# CH32V307VCT6-R2.net
KiCad netlist of a schematic drawn in Altium Designer
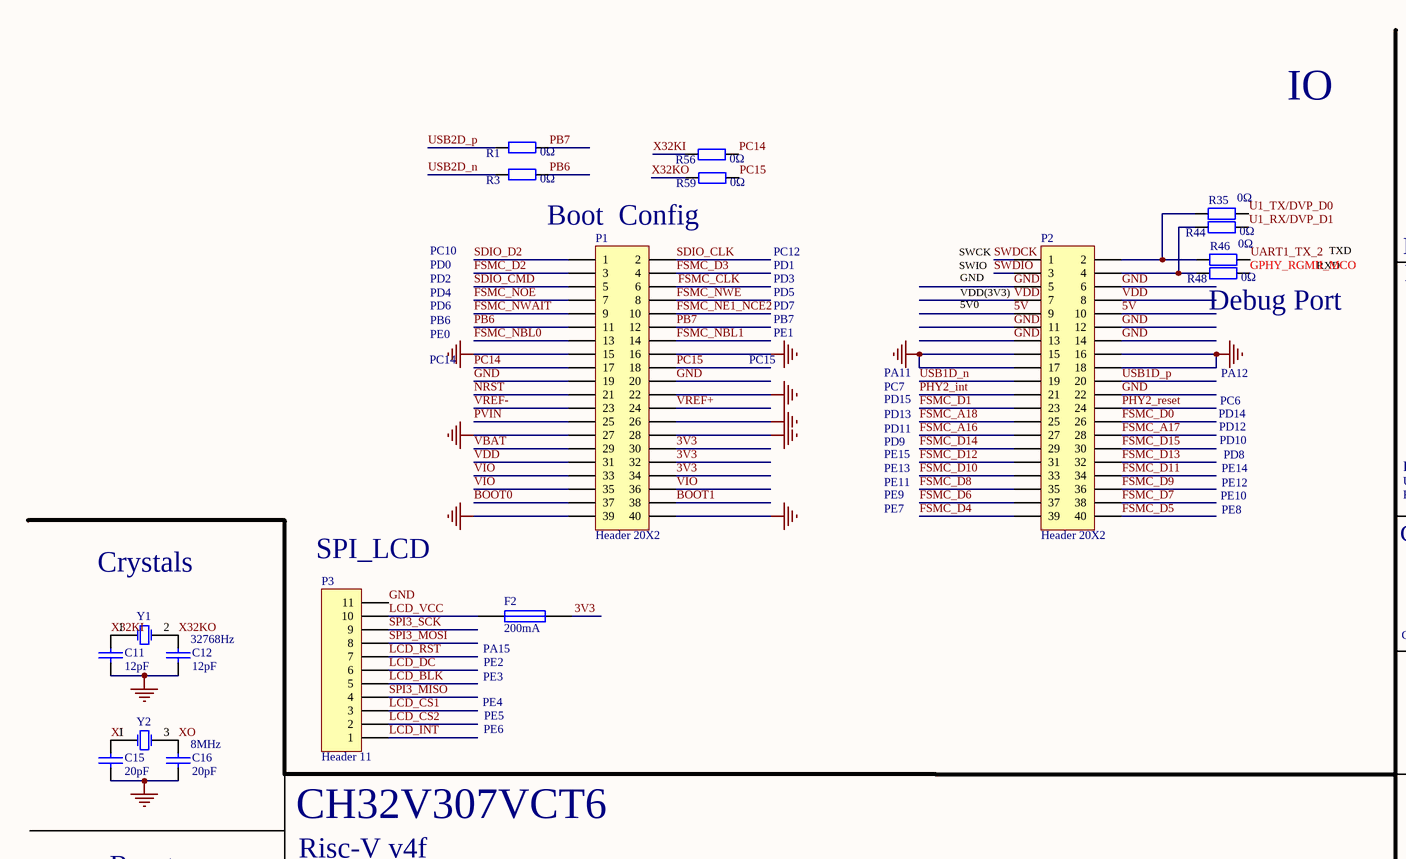
[diagram p0: CH32V307VCT6-R2.SchDoc, top left]
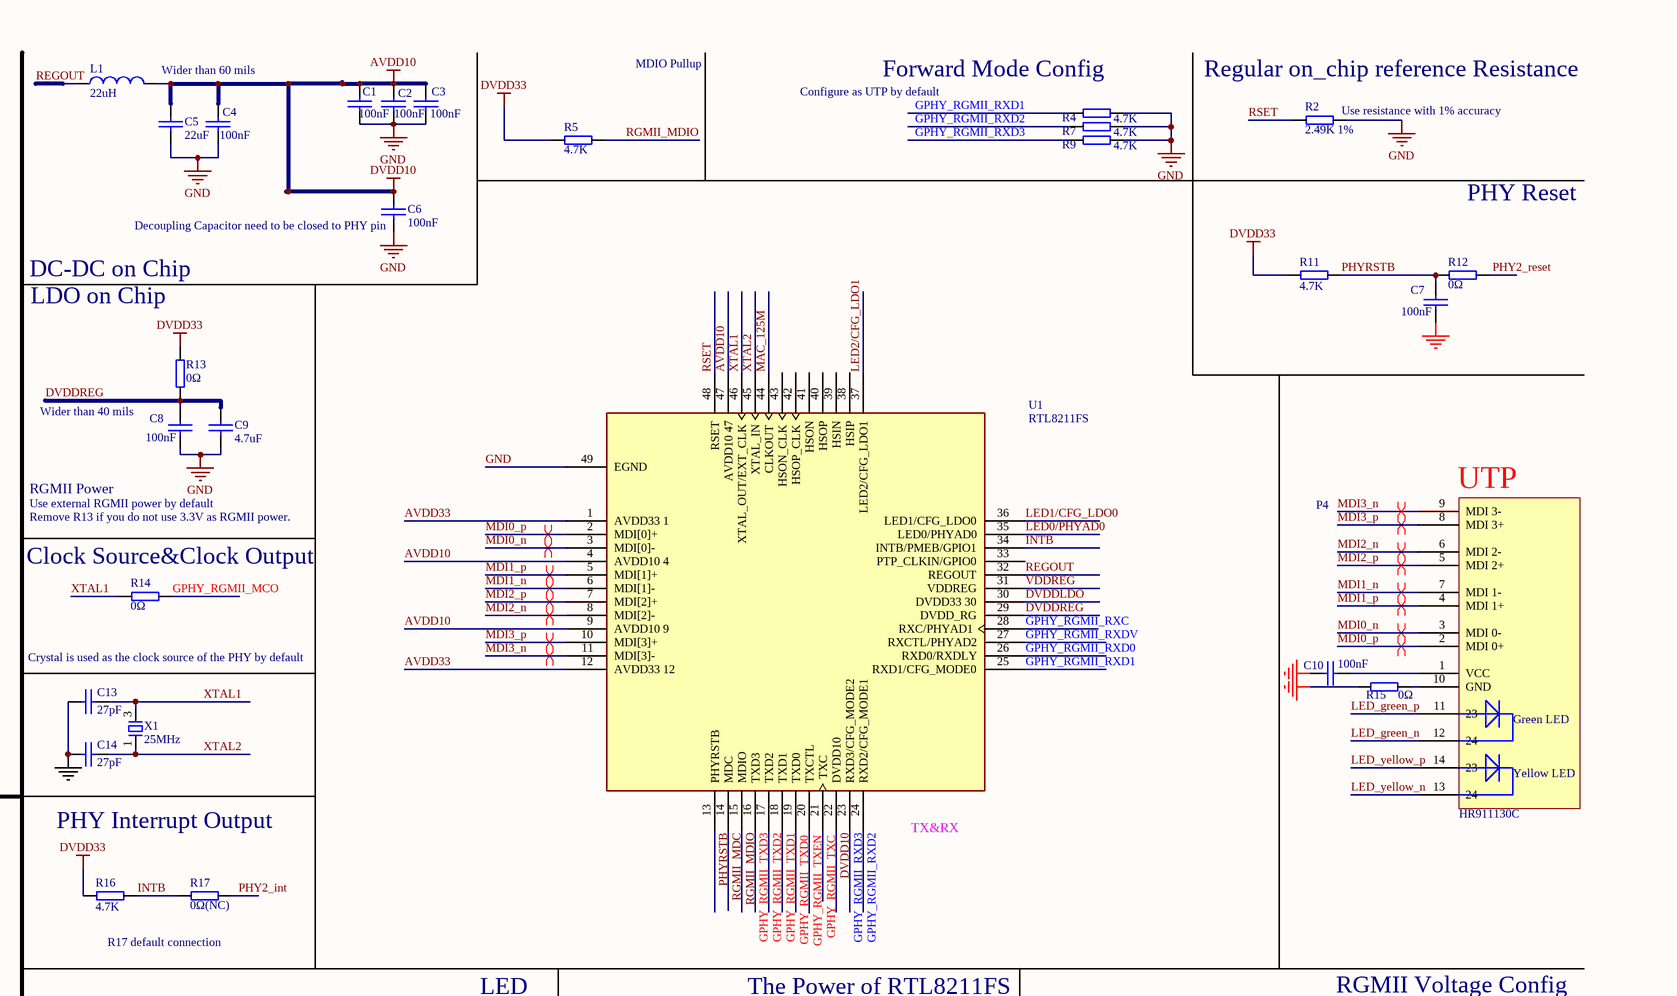
[diagram p1: CH32V307VCT6-R2.SchDoc, top right]
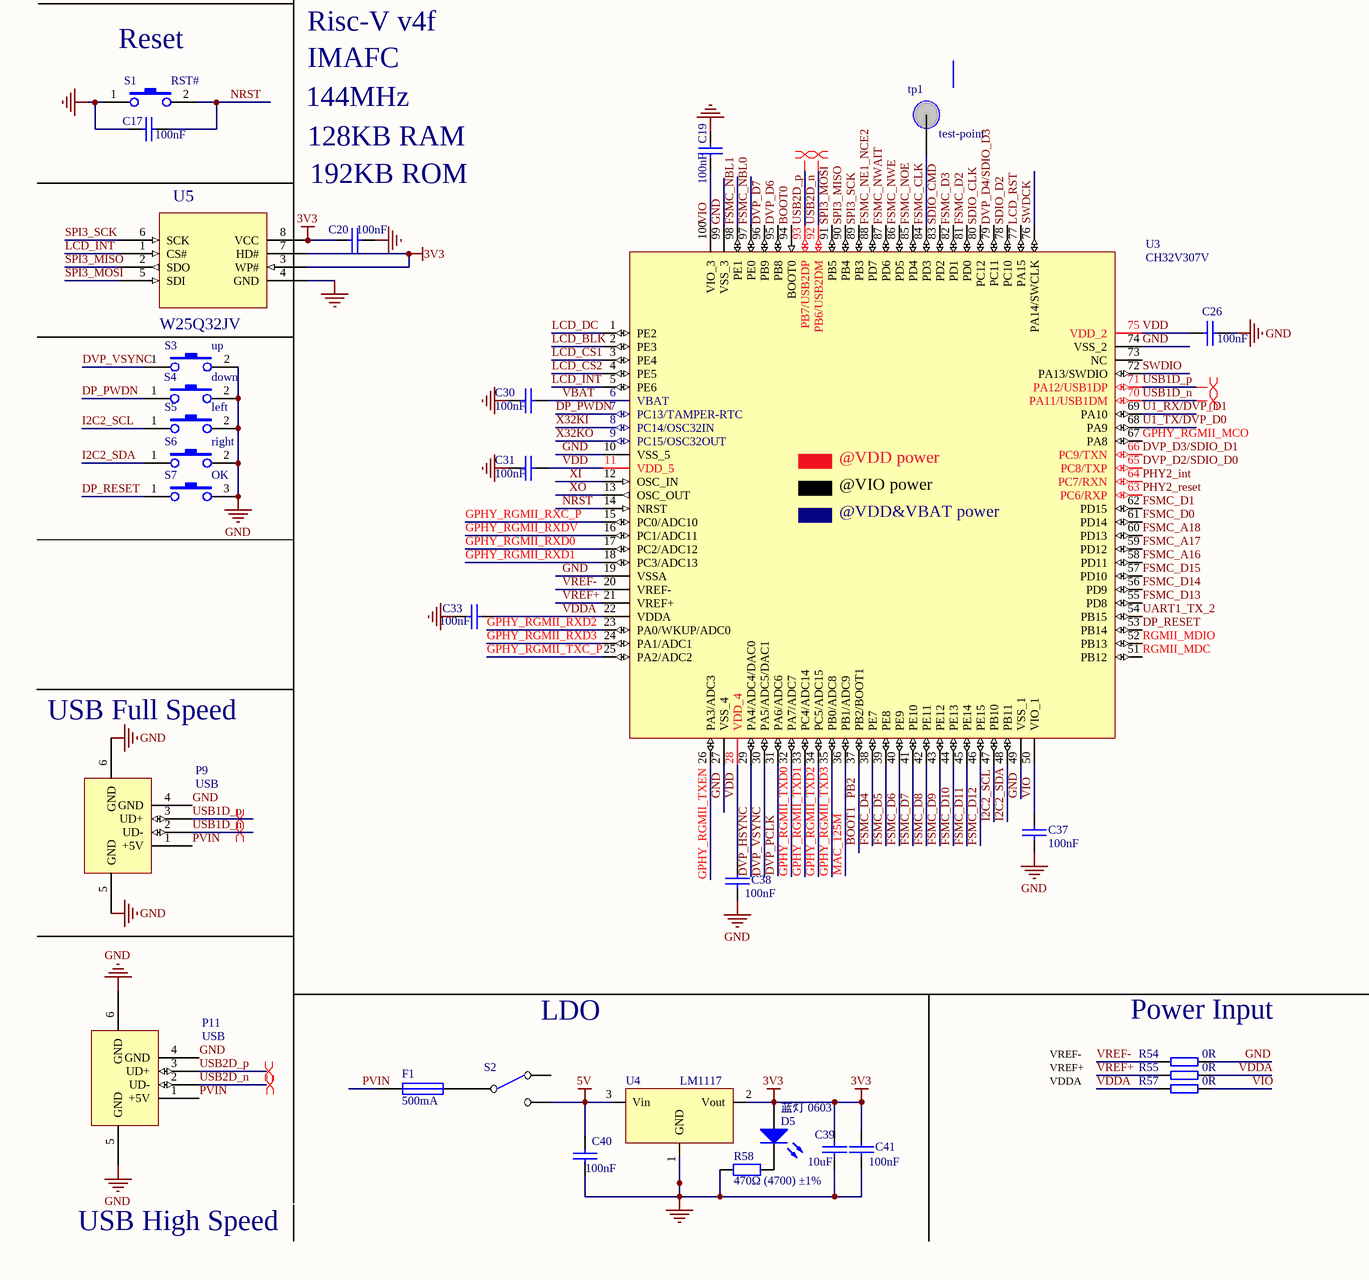
[diagram p2: CH32V307VCT6-R2.SchDoc, bottom left]
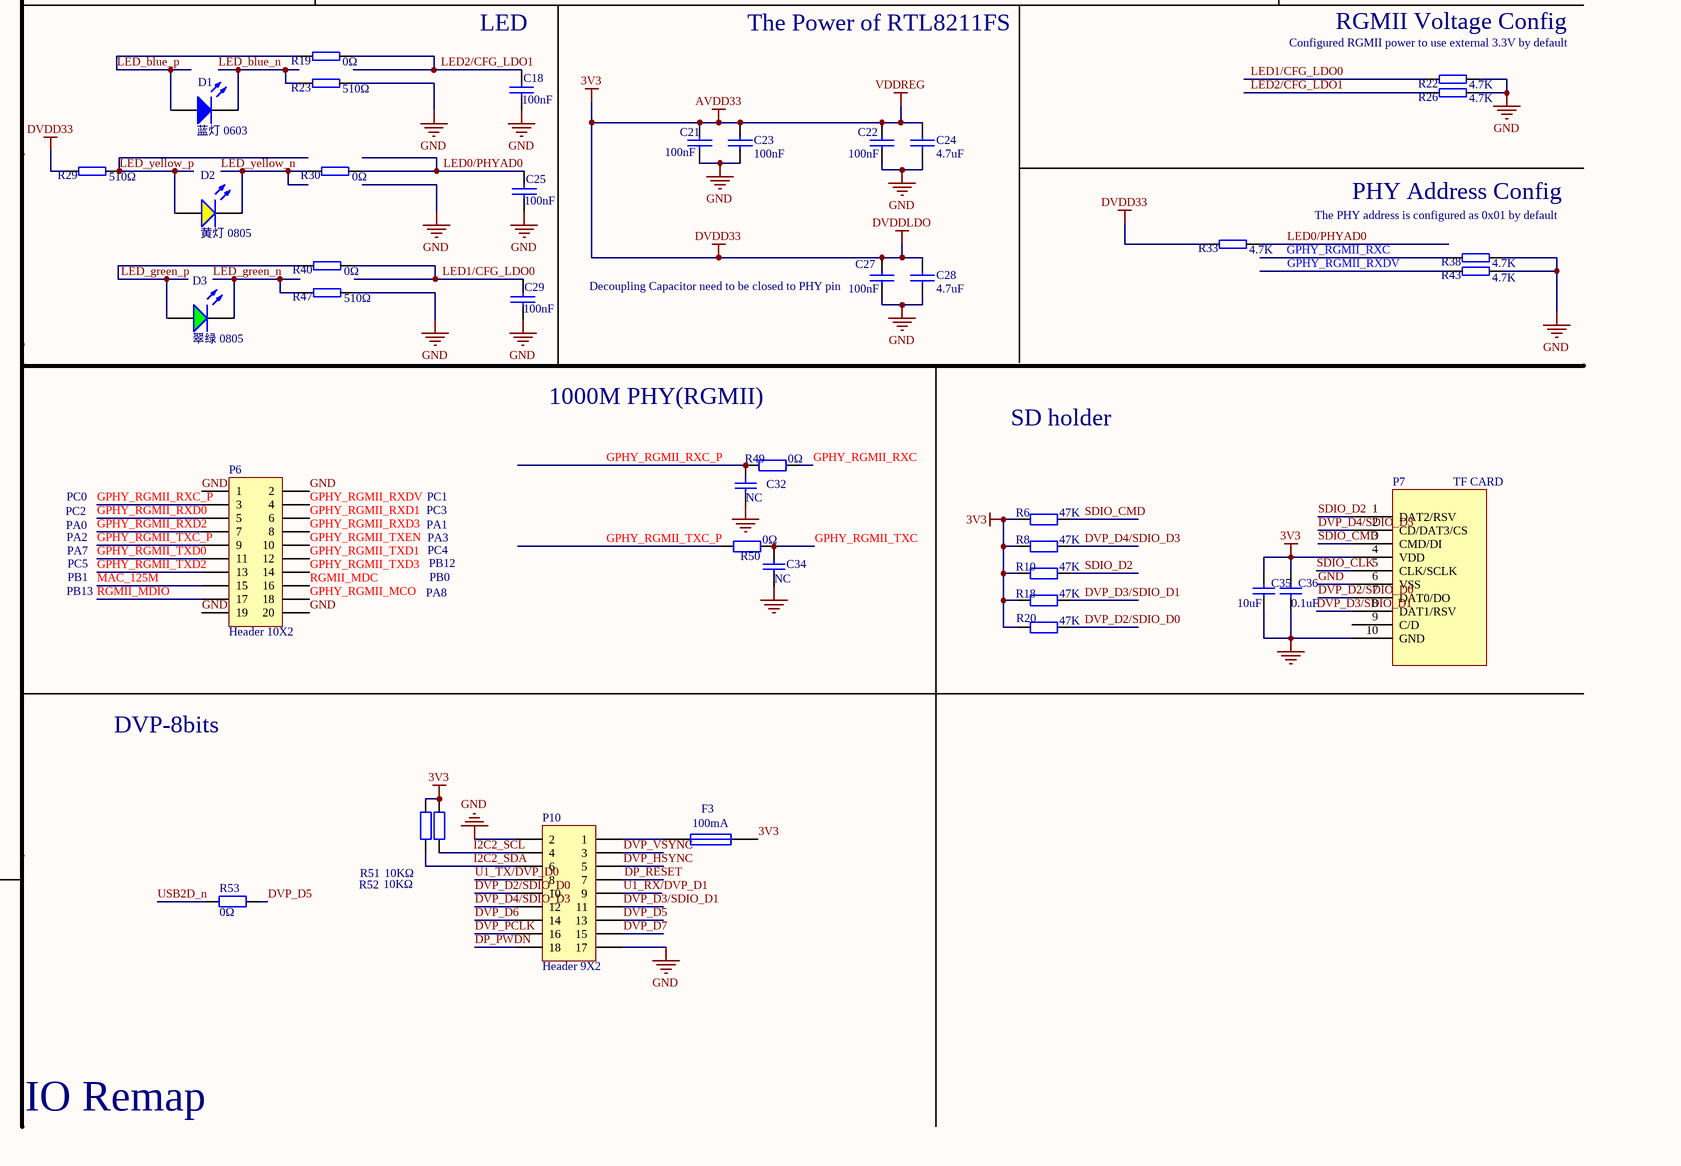
[diagram p3: CH32V307VCT6-R2.SchDoc, bottom right]

(export (version "E")
  (design (tool "Eeschema 10.0.6"))
  (components
    (comp (ref "C1")
      (value "100nF")
      (footprint "0603_C")
      (description "Capacitor")
      (libsource (lib "*") (part "CAP"))
    )
    (comp (ref "C2")
      (value "100nF")
      (footprint "0603_C")
      (description "Capacitor")
      (libsource (lib "*") (part "CAP"))
    )
    (comp (ref "C3")
      (value "100nF")
      (footprint "0603_C")
      (description "Capacitor")
      (libsource (lib "*") (part "CAP"))
    )
    (comp (ref "C4")
      (value "100nF")
      (footprint "0603_C")
      (description "Capacitor")
      (libsource (lib "*") (part "CAP"))
    )
    (comp (ref "C5")
      (value "22uF")
      (footprint "0805_C")
      (description "Capacitor")
      (libsource (lib "wch_sch_others") (part "CAP"))
    )
    (comp (ref "C6")
      (value "100nF")
      (footprint "0603_C")
      (description "Capacitor")
      (libsource (lib "*") (part "CAP"))
    )
    (comp (ref "C7")
      (value "100nF")
      (footprint "0603_C")
      (description "Capacitor")
      (libsource (lib "*") (part "CAP"))
    )
    (comp (ref "C8")
      (value "100nF")
      (footprint "0603_C")
      (description "Capacitor")
      (libsource (lib "*") (part "CAP"))
    )
    (comp (ref "C9")
      (value "4.7uF")
      (footprint "0603_C")
      (description "Capacitor")
      (libsource (lib "wch_sch_others") (part "CAP"))
    )
    (comp (ref "C10")
      (value "100nF")
      (footprint "0603_C")
      (description "Capacitor")
      (libsource (lib "*") (part "CAP"))
    )
    (comp (ref "C11")
      (value "12pF")
      (footprint "0603_C")
      (description "Capacitor")
      (libsource (lib "*") (part "CAP"))
    )
    (comp (ref "C12")
      (value "12pF")
      (footprint "0603_C")
      (description "Capacitor")
      (libsource (lib "*") (part "CAP"))
    )
    (comp (ref "C13")
      (value "27pF")
      (footprint "0603_C")
      (description "Capacitor")
      (libsource (lib "wch_sch_others") (part "CAP"))
    )
    (comp (ref "C14")
      (value "27pF")
      (footprint "0603_C")
      (description "Capacitor")
      (libsource (lib "wch_sch_others") (part "CAP"))
    )
    (comp (ref "C15")
      (value "20pF")
      (footprint "0603_C")
      (description "Capacitor")
      (libsource (lib "*") (part "CAP"))
    )
    (comp (ref "C16")
      (value "20pF")
      (footprint "0603_C")
      (description "Capacitor")
      (libsource (lib "*") (part "CAP"))
    )
    (comp (ref "C17")
      (value "100nF")
      (footprint "0603_C")
      (description "Capacitor")
      (libsource (lib "") (part "CAP_1"))
    )
    (comp (ref "C18")
      (value "100nF")
      (footprint "0603_C")
      (description "Capacitor")
      (libsource (lib "*") (part "CAP"))
    )
    (comp (ref "C19")
      (value "100nF")
      (footprint "0603_C")
      (description "Capacitor")
      (libsource (lib "*") (part "CAP"))
    )
    (comp (ref "C20")
      (value "100nF")
      (footprint "0603_C")
      (description "Capacitor")
      (libsource (lib "*") (part "CAP"))
    )
    (comp (ref "C21")
      (value "100nF")
      (footprint "0603_C")
      (description "Capacitor")
      (libsource (lib "*") (part "CAP"))
    )
    (comp (ref "C22")
      (value "100nF")
      (footprint "0603_C")
      (description "Capacitor")
      (libsource (lib "*") (part "CAP"))
    )
    (comp (ref "C23")
      (value "100nF")
      (footprint "0603_C")
      (description "Capacitor")
      (libsource (lib "*") (part "CAP"))
    )
    (comp (ref "C24")
      (value "4.7uF")
      (footprint "0603_C")
      (description "Capacitor")
      (libsource (lib "wch_sch_others") (part "CAP"))
    )
    (comp (ref "C25")
      (value "100nF")
      (footprint "0603_C")
      (description "Capacitor")
      (libsource (lib "*") (part "CAP"))
    )
    (comp (ref "C26")
      (value "100nF")
      (footprint "0603_C")
      (description "Capacitor")
      (libsource (lib "*") (part "CAP"))
    )
    (comp (ref "C27")
      (value "100nF")
      (footprint "0603_C")
      (description "Capacitor")
      (libsource (lib "*") (part "CAP"))
    )
    (comp (ref "C28")
      (value "4.7uF")
      (footprint "0603_C")
      (description "Capacitor")
      (libsource (lib "wch_sch_others") (part "CAP"))
    )
    (comp (ref "C29")
      (value "100nF")
      (footprint "0603_C")
      (description "Capacitor")
      (libsource (lib "*") (part "CAP"))
    )
    (comp (ref "C30")
      (value "100nF")
      (footprint "0603_C")
      (description "Capacitor")
      (libsource (lib "*") (part "CAP"))
    )
    (comp (ref "C31")
      (value "100nF")
      (footprint "0603_C")
      (description "Capacitor")
      (libsource (lib "*") (part "CAP"))
    )
    (comp (ref "C32")
      (value "NC")
      (footprint "0402_C")
      (description "贴片电容")
      (libsource (lib "Miscellaneous Devices LC") (part "0603 2.7pF (2R7) 0.25pF 50V"))
    )
    (comp (ref "C33")
      (value "100nF")
      (footprint "0603_C")
      (description "Capacitor")
      (libsource (lib "*") (part "CAP"))
    )
    (comp (ref "C34")
      (value "NC")
      (footprint "0402_C")
      (description "贴片电容")
      (libsource (lib "Miscellaneous Devices LC") (part "0603 2.7pF (2R7) 0.25pF 50V"))
    )
    (comp (ref "C35")
      (value "10uF")
      (footprint "0805_C")
      (description "Capacitor")
      (libsource (lib "*") (part "Cap"))
    )
    (comp (ref "C36")
      (value "0.1uF")
      (footprint "0603_C")
      (description "Capacitor")
      (libsource (lib "*") (part "Cap"))
    )
    (comp (ref "C37")
      (value "100nF")
      (footprint "0603_C")
      (description "Capacitor")
      (libsource (lib "*") (part "CAP"))
    )
    (comp (ref "C38")
      (value "100nF")
      (footprint "0603_C")
      (description "Capacitor")
      (libsource (lib "*") (part "CAP"))
    )
    (comp (ref "C39")
      (value "10uF")
      (footprint "0805_C")
      (description "Capacitor")
      (libsource (lib "*") (part "CAP"))
    )
    (comp (ref "C40")
      (value "100nF")
      (footprint "0603_C")
      (description "Capacitor")
      (libsource (lib "*") (part "CAP"))
    )
    (comp (ref "C41")
      (value "100nF")
      (footprint "0603_C")
      (description "Capacitor")
      (libsource (lib "*") (part "CAP"))
    )
    (comp (ref "D1")
      (value "蓝灯 0603")
      (footprint "0603_LED_S1")
      (description "发光二极管")
      (libsource (lib "Miscellaneous Devices LC") (part "0603 蓝灯"))
    )
    (comp (ref "D2")
      (value "黄灯 0805")
      (footprint "0603_LED_S1")
      (description "发光二极管")
      (libsource (lib "Miscellaneous Devices LC") (part "0805 黄灯"))
    )
    (comp (ref "D3")
      (value "翠绿 0805")
      (footprint "0603_LED_S1")
      (description "发光二极管")
      (libsource (lib "Miscellaneous Devices LC") (part "0805 翠绿"))
    )
    (comp (ref "D5")
      (value "蓝灯 0603")
      (footprint "0603_LED_S1")
      (description "发光二极管")
      (libsource (lib "Miscellaneous Devices LC") (part "0603 蓝灯"))
    )
    (comp (ref "F1")
      (value "500mA")
      (footprint "0805")
      (description "Fuse")
      (fields (field (name "PUBLISHER") "Altium Limited"))
      (libsource (lib "Miscellaneous Devices") (part "Fuse 1"))
    )
    (comp (ref "F2")
      (value "200mA")
      (footprint "0805")
      (description "Fuse")
      (fields (field (name "PUBLISHER") "Altium Limited"))
      (libsource (lib "Miscellaneous Devices") (part "Fuse 1"))
    )
    (comp (ref "F3")
      (value "100mA")
      (footprint "0805")
      (description "Fuse")
      (fields (field (name "PUBLISHER") "Altium Limited"))
      (libsource (lib "Miscellaneous Devices") (part "Fuse 1"))
    )
    (comp (ref "L1")
      (value "22uH")
      (footprint "0805")
      (description "Inductor")
      (fields (field (name "PUBLISHER") "Altium Limited"))
      (libsource (lib "Miscellaneous Devices") (part "Inductor"))
    )
    (comp (ref "P1")
      (value "Header 20X2")
      (footprint "HDR2X20")
      (description "Header, 20-Pin, Dual row")
      (fields (field (name "PUBLISHER") "Altium Limited"))
      (libsource (lib "Miscellaneous Connectors") (part "Header 20X2"))
    )
    (comp (ref "P2")
      (value "Header 20X2")
      (footprint "HDR2X20")
      (description "Header, 20-Pin, Dual row")
      (fields (field (name "PUBLISHER") "Altium Limited"))
      (libsource (lib "Miscellaneous Connectors") (part "Header 20X2"))
    )
    (comp (ref "P3")
      (value "Header 11")
      (footprint "HDR1X11")
      (description "Header, 11-Pin")
      (fields (field (name "PUBLISHER") "Altium Limited"))
      (libsource (lib "Miscellaneous Connectors") (part "Header 11"))
    )
    (comp (ref "P4") (value "HR911130C") (footprint "RJ45-1G") (libsource (lib "*") (part "HR911130C")))
    (comp (ref "P6")
      (value "Header 10X2")
      (footprint "HDR2X10")
      (description "Header, 10-Pin, Dual row")
      (fields (field (name "PUBLISHER") "Altium Limited"))
      (libsource (lib "Miscellaneous Connectors") (part "Header 10X2"))
    )
    (comp (ref "P7") (value "TF CARD") (footprint "TF103") (libsource (lib "*") (part "TF_自弹")))
    (comp (ref "P9")
      (value "USB")
      (footprint "USBAF")
      (description "USB Port")
      (libsource (lib "CHXXX") (part "USB"))
    )
    (comp (ref "P10")
      (value "Header 9X2")
      (footprint "HDR2X9")
      (description "Header, 9-Pin, Dual row")
      (fields (field (name "PUBLISHER") "Altium Limited"))
      (libsource (lib "Miscellaneous Connectors") (part "Header 9X2"))
    )
    (comp (ref "P11")
      (value "USB")
      (footprint "USBAF")
      (description "USB Port")
      (libsource (lib "CHXXX") (part "USB"))
    )
    (comp (ref "R1")
      (value "0Ω")
      (footprint "0402")
      (description "贴片电阻")
      (libsource (lib "Miscellaneous Devices LC") (part "0402 0Ω (0R0) 1%"))
    )
    (comp (ref "R2") (value "2.49K 1%") (footprint "0603_R") (libsource (lib "wch_sch_others") (part "Res")))
    (comp (ref "R3")
      (value "0Ω")
      (footprint "0402")
      (description "贴片电阻")
      (libsource (lib "Miscellaneous Devices LC") (part "0402 0Ω (0R0) 1%"))
    )
    (comp (ref "R4") (value "4.7K") (footprint "0603_R") (libsource (lib "wch_sch_others") (part "Res")))
    (comp (ref "R5") (value "4.7K") (footprint "0603_R") (libsource (lib "wch_sch_others") (part "Res")))
    (comp (ref "R6")
      (value "47K")
      (footprint "0603_R")
      (description "Resistor")
      (libsource (lib "Miscellaneous Devices") (part "Res2"))
    )
    (comp (ref "R7") (value "4.7K") (footprint "0603_R") (libsource (lib "wch_sch_others") (part "Res")))
    (comp (ref "R8")
      (value "47K")
      (footprint "0603_R")
      (description "Resistor")
      (libsource (lib "Miscellaneous Devices") (part "Res2"))
    )
    (comp (ref "R9") (value "4.7K") (footprint "0603_R") (libsource (lib "wch_sch_others") (part "Res")))
    (comp (ref "R10")
      (value "47K")
      (footprint "0603_R")
      (description "Resistor")
      (libsource (lib "Miscellaneous Devices") (part "Res2"))
    )
    (comp (ref "R11") (value "4.7K") (footprint "0603_R") (libsource (lib "wch_sch_others") (part "Res")))
    (comp (ref "R12") (value "0Ω") (footprint "0603_R") (libsource (lib "wch_sch_others") (part "Res")))
    (comp (ref "R13") (value "0Ω") (footprint "0603_R") (libsource (lib "wch_sch_others") (part "Res")))
    (comp (ref "R14") (value "0Ω") (footprint "0603_R") (libsource (lib "wch_sch_others") (part "Res")))
    (comp (ref "R15") (value "0Ω") (footprint "0603_R") (libsource (lib "wch_sch_others") (part "Res")))
    (comp (ref "R16") (value "4.7K") (footprint "0603_R") (libsource (lib "wch_sch_others") (part "Res")))
    (comp (ref "R17") (value "0Ω(NC)") (footprint "0603_R") (libsource (lib "wch_sch_others") (part "Res")))
    (comp (ref "R18")
      (value "47K")
      (footprint "0603_R")
      (description "Resistor")
      (libsource (lib "Miscellaneous Devices") (part "Res2"))
    )
    (comp (ref "R19") (value "0Ω") (footprint "0603_R") (libsource (lib "wch_sch_others") (part "Res")))
    (comp (ref "R20")
      (value "47K")
      (footprint "0603_R")
      (description "Resistor")
      (libsource (lib "Miscellaneous Devices") (part "Res2"))
    )
    (comp (ref "R22") (value "4.7K") (footprint "0603_R") (libsource (lib "wch_sch_others") (part "Res")))
    (comp (ref "R23") (value "510Ω") (footprint "0603_R") (libsource (lib "wch_sch_others") (part "Res")))
    (comp (ref "R26") (value "4.7K") (footprint "0603_R") (libsource (lib "wch_sch_others") (part "Res")))
    (comp (ref "R29") (value "510Ω") (footprint "0603_R") (libsource (lib "wch_sch_others") (part "Res")))
    (comp (ref "R30") (value "0Ω") (footprint "0603_R") (libsource (lib "wch_sch_others") (part "Res")))
    (comp (ref "R33") (value "4.7K") (footprint "0603_R") (libsource (lib "wch_sch_others") (part "Res")))
    (comp (ref "R35")
      (value "0Ω")
      (footprint "0402_R")
      (description "贴片电阻")
      (libsource (lib "Miscellaneous Devices LC") (part "0402 0Ω (0R0) 1%"))
    )
    (comp (ref "R38") (value "4.7K") (footprint "0603_R") (libsource (lib "wch_sch_others") (part "Res")))
    (comp (ref "R40") (value "0Ω") (footprint "0603_R") (libsource (lib "wch_sch_others") (part "Res")))
    (comp (ref "R43") (value "4.7K") (footprint "0603_R") (libsource (lib "wch_sch_others") (part "Res")))
    (comp (ref "R44")
      (value "0Ω")
      (footprint "0402_R")
      (description "贴片电阻")
      (libsource (lib "Miscellaneous Devices LC") (part "0402 0Ω (0R0) 1%"))
    )
    (comp (ref "R46")
      (value "0Ω")
      (footprint "0402_R")
      (description "贴片电阻")
      (libsource (lib "Miscellaneous Devices LC") (part "0402 0Ω (0R0) 1%"))
    )
    (comp (ref "R47") (value "510Ω") (footprint "0603_R") (libsource (lib "wch_sch_others") (part "Res")))
    (comp (ref "R48")
      (value "0Ω")
      (footprint "0402_R")
      (description "贴片电阻")
      (libsource (lib "Miscellaneous Devices LC") (part "0402 0Ω (0R0) 1%"))
    )
    (comp (ref "R49")
      (value "0Ω")
      (footprint "0402_R")
      (description "Resistor")
      (libsource (lib "Miscellaneous Devices") (part "Res2"))
    )
    (comp (ref "R50")
      (value "0Ω")
      (footprint "0402_R")
      (description "Resistor")
      (libsource (lib "Miscellaneous Devices") (part "Res2"))
    )
    (comp (ref "R51")
      (value "10KΩ")
      (footprint "0603_R")
      (description "贴片电阻")
      (libsource (lib "Miscellaneous Devices LC") (part "0603 10KΩ (1002) 1%"))
    )
    (comp (ref "R52")
      (value "10KΩ")
      (footprint "0603_R")
      (description "贴片电阻")
      (libsource (lib "Miscellaneous Devices LC") (part "0603 10KΩ (1002) 1%"))
    )
    (comp (ref "R53")
      (value "0Ω")
      (footprint "0402")
      (description "贴片电阻")
      (libsource (lib "Miscellaneous Devices LC") (part "0402 0Ω (0R0) 1%"))
    )
    (comp (ref "R54") (value "0R") (footprint "0402") (libsource (lib "*") (part "R")))
    (comp (ref "R55") (value "0R") (footprint "0402") (libsource (lib "*") (part "R")))
    (comp (ref "R56")
      (value "0Ω")
      (footprint "0402")
      (description "贴片电阻")
      (libsource (lib "Miscellaneous Devices LC") (part "0402 0Ω (0R0) 1%"))
    )
    (comp (ref "R57") (value "0R") (footprint "0402") (libsource (lib "*") (part "R")))
    (comp (ref "R58")
      (value "470Ω (4700) ±1%")
      (footprint "0603_R")
      (description "贴片电阻")
      (libsource (lib "Miscellaneous Devices LC") (part "0603 470Ω (4700) 1%"))
    )
    (comp (ref "R59")
      (value "0Ω")
      (footprint "0402")
      (description "贴片电阻")
      (libsource (lib "Miscellaneous Devices LC") (part "0402 0Ω (0R0) 1%"))
    )
    (comp (ref "S1") (value "RST#") (footprint "SMD_6.1x3.65x2.5mm-KEY") (libsource (lib "") (part "KEY1_1")))
    (comp (ref "S2")
      (value "SW SPDT")
      (footprint "Horizontal Slide Switch_8.7x4.4mm-2D")
      (libsource (lib "*") (part "SW SPDT"))
    )
    (comp (ref "S3") (value "up") (footprint "SMD_6.1x3.65x2.5mm-KEY") (libsource (lib "") (part "KEY1_1")))
    (comp (ref "S4") (value "down") (footprint "SMD_6.1x3.65x2.5mm-KEY") (libsource (lib "") (part "KEY1_1")))
    (comp (ref "S5") (value "left") (footprint "SMD_6.1x3.65x2.5mm-KEY") (libsource (lib "") (part "KEY1_1")))
    (comp (ref "S6")
      (value "right")
      (footprint "SMD_6.1x3.65x2.5mm-KEY")
      (libsource (lib "") (part "KEY1_1"))
    )
    (comp (ref "S7") (value "OK") (footprint "KEYD") (libsource (lib "wch_sch_others") (part "KEY1")))
    (comp (ref "tp1")
      (value "test-point")
      (footprint "POINT")
      (description "测试点")
      (libsource (lib "五向开关") (part "test-point"))
    )
    (comp (ref "U1")
      (value "RTL8211FS")
      (footprint "QFN-48_6x6x04P")
      (description "千兆以太网物理层芯片")
      (libsource (lib "wch_sch_others") (part "RTL8211FS(I)"))
    )
    (comp (ref "U3")
      (value "CH32V307V")
      (footprint "LQFP100")
      (description "RISC-V FPU HD-MCU, 144MHz, USB_480M, USB OTG, 1000M Ethernet MAC, 2*CAN, FSMC+DVP")
      (libsource (lib "CHXXX") (part "CH32V307V"))
    )
    (comp (ref "U4")
      (value "LM1117")
      (footprint "SOT-223")
      (libsource (lib "wch_sch_others") (part "6219P33M"))
    )
    (comp (ref "U5")
      (value "W25Q32JV")
      (footprint "SOIC-8_208mil")
      (libsource (lib "*") (part "Pro89C.tmp_25F512_2"))
    )
    (comp (ref "X1")
      (value "25MHz")
      (footprint "SMD-3225_4P")
      (description "2脚无源脚晶振")
      (libsource (lib "10.1 - 保险丝-晶振") (part "XTAL-2P"))
    )
    (comp (ref "Y1")
      (value "32768Hz")
      (footprint "FC-135")
      (description "Crystal Oscillator")
      (fields (field (name "PUBLISHER") "Altium Limited"))
      (libsource (lib "*") (part "XTAL"))
    )
    (comp (ref "Y2")
      (value "8MHz")
      (footprint "SMD-3225_4P")
      (description "Crystal Oscillator")
      (fields (field (name "PUBLISHER") "Altium Limited"))
      (libsource (lib "") (part "XTAL_1"))
    )
  )
  (nets
    (net (code "2") (name "/BOOT0") (class "Default")
      (node (ref "P1") (pin "37") (pinfunction "37_37") (pintype "passive"))
      (node (ref "U3") (pin "94") (pinfunction "BOOT0_94") (pintype "input"))
    )
    (net (code "3") (name "/BOOT1") (class "Default")
      (node (ref "P1") (pin "38") (pinfunction "38_38") (pintype "passive"))
      (node (ref "U3") (pin "37") (pinfunction "PB2/BOOT1_37") (pintype "bidirectional"))
    )
    (net (code "4") (name "/DP_PWDN") (class "Default")
      (node (ref "P10") (pin "18") (pinfunction "18_18") (pintype "passive"))
      (node (ref "S4") (pin "1") (pinfunction "1_1") (pintype "passive"))
      (node (ref "U3") (pin "7") (pinfunction "PC13/TAMPER-RTC_7") (pintype "bidirectional"))
    )
    (net (code "5") (name "/DP_RESET") (class "Default")
      (node (ref "P10") (pin "7") (pinfunction "7_7") (pintype "passive"))
      (node (ref "S7") (pin "1") (pinfunction "1_1") (pintype "passive"))
      (node (ref "U3") (pin "53") (pinfunction "PB14_53") (pintype "bidirectional"))
    )
    (net (code "6") (name "/DVDDREG") (class "Default")
      (node (ref "C8") (pin "2") (pinfunction "2_2") (pintype "passive"))
      (node (ref "C9") (pin "2") (pinfunction "2_2") (pintype "passive"))
      (node (ref "R13") (pin "1") (pintype "passive"))
      (node (ref "U1") (pin "29") (pinfunction "DVDD_RG_29") (pintype "power_in"))
    )
    (net (code "7") (name "/DVP_D2{slash}SDIO_D0") (class "Default")
      (node (ref "P10") (pin "10") (pinfunction "10_10") (pintype "passive"))
      (node (ref "P7") (pin "7") (pinfunction "DAT0/DO_7") (pintype "passive"))
      (node (ref "R20") (pin "1") (pinfunction "1_1") (pintype "passive"))
      (node (ref "U3") (pin "65") (pinfunction "PC8/TXP_65") (pintype "bidirectional"))
    )
    (net (code "8") (name "/DVP_D3{slash}SDIO_D1") (class "Default")
      (node (ref "P10") (pin "11") (pinfunction "11_11") (pintype "passive"))
      (node (ref "P7") (pin "8") (pinfunction "DAT1/RSV_8") (pintype "passive"))
      (node (ref "R18") (pin "1") (pinfunction "1_1") (pintype "passive"))
      (node (ref "U3") (pin "66") (pinfunction "PC9/TXN_66") (pintype "bidirectional"))
    )
    (net (code "9") (name "/DVP_D4{slash}SDIO_D3") (class "Default")
      (node (ref "P10") (pin "12") (pinfunction "12_12") (pintype "passive"))
      (node (ref "P7") (pin "2") (pinfunction "CD/DAT3/CS_2") (pintype "passive"))
      (node (ref "R8") (pin "1") (pinfunction "1_1") (pintype "passive"))
      (node (ref "U3") (pin "79") (pinfunction "PC11_79") (pintype "bidirectional"))
    )
    (net (code "10") (name "/DVP_D5") (class "Default")
      (node (ref "P10") (pin "13") (pinfunction "13_13") (pintype "passive"))
      (node (ref "R53") (pin "2") (pinfunction "2_2") (pintype "passive"))
    )
    (net (code "11") (name "/DVP_D6") (class "Default")
      (node (ref "P10") (pin "14") (pinfunction "14_14") (pintype "passive"))
      (node (ref "U3") (pin "95") (pinfunction "PB8_95") (pintype "bidirectional"))
    )
    (net (code "12") (name "/DVP_D7") (class "Default")
      (node (ref "P10") (pin "15") (pinfunction "15_15") (pintype "passive"))
      (node (ref "U3") (pin "96") (pinfunction "PB9_96") (pintype "bidirectional"))
    )
    (net (code "13") (name "/DVP_HSYNC") (class "Default")
      (node (ref "P10") (pin "5") (pinfunction "5_5") (pintype "passive"))
      (node (ref "U3") (pin "29") (pinfunction "PA4/ADC4/DAC0_29") (pintype "bidirectional"))
    )
    (net (code "14") (name "/DVP_PCLK") (class "Default")
      (node (ref "P10") (pin "16") (pinfunction "16_16") (pintype "passive"))
      (node (ref "U3") (pin "31") (pinfunction "PA6/ADC6_31") (pintype "bidirectional"))
    )
    (net (code "15") (name "/DVP_VSYNC") (class "Default")
      (node (ref "P10") (pin "3") (pinfunction "3_3") (pintype "passive"))
      (node (ref "S3") (pin "1") (pinfunction "1_1") (pintype "passive"))
      (node (ref "U3") (pin "30") (pinfunction "PA5/ADC5/DAC1_30") (pintype "bidirectional"))
    )
    (net (code "16") (name "/FSMC_A16") (class "Default")
      (node (ref "P2") (pin "27") (pinfunction "27_27") (pintype "passive"))
      (node (ref "U3") (pin "58") (pinfunction "PD11_58") (pintype "bidirectional"))
    )
    (net (code "17") (name "/FSMC_A17") (class "Default")
      (node (ref "P2") (pin "28") (pinfunction "28_28") (pintype "passive"))
      (node (ref "U3") (pin "59") (pinfunction "PD12_59") (pintype "bidirectional"))
    )
    (net (code "18") (name "/FSMC_A18") (class "Default")
      (node (ref "P2") (pin "25") (pinfunction "25_25") (pintype "passive"))
      (node (ref "U3") (pin "60") (pinfunction "PD13_60") (pintype "bidirectional"))
    )
    (net (code "19") (name "/FSMC_CLK") (class "Default")
      (node (ref "P1") (pin "6") (pinfunction "6_6") (pintype "passive"))
      (node (ref "U3") (pin "84") (pinfunction "PD3_84") (pintype "bidirectional"))
      (node (ref "tp1") (pin "1") (pinfunction "point_1") (pintype "passive"))
    )
    (net (code "20") (name "/FSMC_D0") (class "Default")
      (node (ref "P2") (pin "26") (pinfunction "26_26") (pintype "passive"))
      (node (ref "U3") (pin "61") (pinfunction "PD14_61") (pintype "bidirectional"))
    )
    (net (code "21") (name "/FSMC_D1") (class "Default")
      (node (ref "P2") (pin "23") (pinfunction "23_23") (pintype "passive"))
      (node (ref "U3") (pin "62") (pinfunction "PD15_62") (pintype "bidirectional"))
    )
    (net (code "22") (name "/FSMC_D2") (class "Default")
      (node (ref "P1") (pin "3") (pinfunction "3_3") (pintype "passive"))
      (node (ref "U3") (pin "81") (pinfunction "PD0_81") (pintype "bidirectional"))
    )
    (net (code "23") (name "/FSMC_D3") (class "Default")
      (node (ref "P1") (pin "4") (pinfunction "4_4") (pintype "passive"))
      (node (ref "U3") (pin "82") (pinfunction "PD1_82") (pintype "bidirectional"))
    )
    (net (code "24") (name "/FSMC_D4") (class "Default")
      (node (ref "P2") (pin "39") (pinfunction "39_39") (pintype "passive"))
      (node (ref "U3") (pin "38") (pinfunction "PE7_38") (pintype "bidirectional"))
    )
    (net (code "25") (name "/FSMC_D5") (class "Default")
      (node (ref "P2") (pin "40") (pinfunction "40_40") (pintype "passive"))
      (node (ref "U3") (pin "39") (pinfunction "PE8_39") (pintype "bidirectional"))
    )
    (net (code "26") (name "/FSMC_D6") (class "Default")
      (node (ref "P2") (pin "37") (pinfunction "37_37") (pintype "passive"))
      (node (ref "U3") (pin "40") (pinfunction "PE9_40") (pintype "bidirectional"))
    )
    (net (code "27") (name "/FSMC_D7") (class "Default")
      (node (ref "P2") (pin "38") (pinfunction "38_38") (pintype "passive"))
      (node (ref "U3") (pin "41") (pinfunction "PE10_41") (pintype "bidirectional"))
    )
    (net (code "28") (name "/FSMC_D8") (class "Default")
      (node (ref "P2") (pin "35") (pinfunction "35_35") (pintype "passive"))
      (node (ref "U3") (pin "42") (pinfunction "PE11_42") (pintype "bidirectional"))
    )
    (net (code "29") (name "/FSMC_D9") (class "Default")
      (node (ref "P2") (pin "36") (pinfunction "36_36") (pintype "passive"))
      (node (ref "U3") (pin "43") (pinfunction "PE12_43") (pintype "bidirectional"))
    )
    (net (code "30") (name "/FSMC_D10") (class "Default")
      (node (ref "P2") (pin "33") (pinfunction "33_33") (pintype "passive"))
      (node (ref "U3") (pin "44") (pinfunction "PE13_44") (pintype "bidirectional"))
    )
    (net (code "31") (name "/FSMC_D11") (class "Default")
      (node (ref "P2") (pin "34") (pinfunction "34_34") (pintype "passive"))
      (node (ref "U3") (pin "45") (pinfunction "PE14_45") (pintype "bidirectional"))
    )
    (net (code "32") (name "/FSMC_D12") (class "Default")
      (node (ref "P2") (pin "31") (pinfunction "31_31") (pintype "passive"))
      (node (ref "U3") (pin "46") (pinfunction "PE15_46") (pintype "bidirectional"))
    )
    (net (code "33") (name "/FSMC_D13") (class "Default")
      (node (ref "P2") (pin "32") (pinfunction "32_32") (pintype "passive"))
      (node (ref "U3") (pin "55") (pinfunction "PD8_55") (pintype "bidirectional"))
    )
    (net (code "34") (name "/FSMC_D14") (class "Default")
      (node (ref "P2") (pin "29") (pinfunction "29_29") (pintype "passive"))
      (node (ref "U3") (pin "56") (pinfunction "PD9_56") (pintype "bidirectional"))
    )
    (net (code "35") (name "/FSMC_D15") (class "Default")
      (node (ref "P2") (pin "30") (pinfunction "30_30") (pintype "passive"))
      (node (ref "U3") (pin "57") (pinfunction "PD10_57") (pintype "bidirectional"))
    )
    (net (code "36") (name "/FSMC_NBL0") (class "Default")
      (node (ref "P1") (pin "13") (pinfunction "13_13") (pintype "passive"))
      (node (ref "U3") (pin "97") (pinfunction "PE0_97") (pintype "bidirectional"))
    )
    (net (code "37") (name "/FSMC_NBL1") (class "Default")
      (node (ref "P1") (pin "14") (pinfunction "14_14") (pintype "passive"))
      (node (ref "U3") (pin "98") (pinfunction "PE1_98") (pintype "bidirectional"))
    )
    (net (code "38") (name "/FSMC_NE1_NCE2") (class "Default")
      (node (ref "P1") (pin "10") (pinfunction "10_10") (pintype "passive"))
      (node (ref "U3") (pin "88") (pinfunction "PD7_88") (pintype "bidirectional"))
    )
    (net (code "39") (name "/FSMC_NOE") (class "Default")
      (node (ref "P1") (pin "7") (pinfunction "7_7") (pintype "passive"))
      (node (ref "U3") (pin "85") (pinfunction "PD4_85") (pintype "bidirectional"))
    )
    (net (code "40") (name "/FSMC_NWAIT") (class "Default")
      (node (ref "P1") (pin "9") (pinfunction "9_9") (pintype "passive"))
      (node (ref "U3") (pin "87") (pinfunction "PD6_87") (pintype "bidirectional"))
    )
    (net (code "41") (name "/FSMC_NWE") (class "Default")
      (node (ref "P1") (pin "8") (pinfunction "8_8") (pintype "passive"))
      (node (ref "U3") (pin "86") (pinfunction "PD5_86") (pintype "bidirectional"))
    )
    (net (code "42") (name "/GPHY_RGMII_MCO") (class "Default")
      (node (ref "P6") (pin "18") (pinfunction "18_18") (pintype "passive"))
      (node (ref "R14") (pin "2") (pintype "passive"))
      (node (ref "R48") (pin "2") (pinfunction "2_2") (pintype "passive"))
      (node (ref "U3") (pin "67") (pinfunction "PA8_67") (pintype "bidirectional"))
    )
    (net (code "43") (name "/GPHY_RGMII_RXC") (class "Default")
      (node (ref "R38") (pin "1") (pintype "passive"))
      (node (ref "R49") (pin "1") (pinfunction "1_1") (pintype "passive"))
      (node (ref "U1") (pin "28") (pinfunction "RXC/PHYAD1_28") (pintype "passive"))
    )
    (net (code "44") (name "/GPHY_RGMII_RXC_P") (class "Default")
      (node (ref "C32") (pin "2") (pinfunction "2_2") (pintype "passive"))
      (node (ref "P6") (pin "3") (pinfunction "3_3") (pintype "passive"))
      (node (ref "R49") (pin "2") (pinfunction "2_2") (pintype "passive"))
      (node (ref "U3") (pin "15") (pinfunction "PC0/ADC10_15") (pintype "bidirectional"))
    )
    (net (code "45") (name "/GPHY_RGMII_RXD0") (class "Default")
      (node (ref "P6") (pin "5") (pinfunction "5_5") (pintype "passive"))
      (node (ref "U1") (pin "26") (pinfunction "RXD0/RXDLY_26") (pintype "passive"))
      (node (ref "U3") (pin "17") (pinfunction "PC2/ADC12_17") (pintype "bidirectional"))
    )
    (net (code "46") (name "/GPHY_RGMII_RXD1") (class "Default")
      (node (ref "P6") (pin "6") (pinfunction "6_6") (pintype "passive"))
      (node (ref "R4") (pin "1") (pintype "passive"))
      (node (ref "U1") (pin "25") (pinfunction "RXD1/CFG_MODE0_25") (pintype "passive"))
      (node (ref "U3") (pin "18") (pinfunction "PC3/ADC13_18") (pintype "bidirectional"))
    )
    (net (code "47") (name "/GPHY_RGMII_RXD2") (class "Default")
      (node (ref "P6") (pin "7") (pinfunction "7_7") (pintype "passive"))
      (node (ref "R7") (pin "1") (pintype "passive"))
      (node (ref "U1") (pin "24") (pinfunction "RXD2/CFG_MODE1_24") (pintype "passive"))
      (node (ref "U3") (pin "23") (pinfunction "PA0/WKUP/ADC0_23") (pintype "bidirectional"))
    )
    (net (code "48") (name "/GPHY_RGMII_RXD3") (class "Default")
      (node (ref "P6") (pin "8") (pinfunction "8_8") (pintype "passive"))
      (node (ref "R9") (pin "1") (pintype "passive"))
      (node (ref "U1") (pin "23") (pinfunction "RXD3/CFG_MODE2_23") (pintype "passive"))
      (node (ref "U3") (pin "24") (pinfunction "PA1/ADC1_24") (pintype "bidirectional"))
    )
    (net (code "49") (name "/GPHY_RGMII_RXDV") (class "Default")
      (node (ref "P6") (pin "4") (pinfunction "4_4") (pintype "passive"))
      (node (ref "R43") (pin "1") (pintype "passive"))
      (node (ref "U1") (pin "27") (pinfunction "RXCTL/PHYAD2_27") (pintype "passive"))
      (node (ref "U3") (pin "16") (pinfunction "PC1/ADC11_16") (pintype "bidirectional"))
    )
    (net (code "50") (name "/GPHY_RGMII_TXC") (class "Default")
      (node (ref "C34") (pin "2") (pinfunction "2_2") (pintype "passive"))
      (node (ref "R50") (pin "1") (pinfunction "1_1") (pintype "passive"))
      (node (ref "U1") (pin "21") (pinfunction "TXC_21") (pintype "passive"))
    )
    (net (code "51") (name "/GPHY_RGMII_TXC_P") (class "Default")
      (node (ref "P6") (pin "9") (pinfunction "9_9") (pintype "passive"))
      (node (ref "R50") (pin "2") (pinfunction "2_2") (pintype "passive"))
      (node (ref "U3") (pin "25") (pinfunction "PA2/ADC2_25") (pintype "bidirectional"))
    )
    (net (code "52") (name "/GPHY_RGMII_TXD0") (class "Default")
      (node (ref "P6") (pin "11") (pinfunction "11_11") (pintype "passive"))
      (node (ref "U1") (pin "19") (pinfunction "TXD0_19") (pintype "passive"))
      (node (ref "U3") (pin "32") (pinfunction "PA7/ADC7_32") (pintype "bidirectional"))
    )
    (net (code "53") (name "/GPHY_RGMII_TXD1") (class "Default")
      (node (ref "P6") (pin "12") (pinfunction "12_12") (pintype "passive"))
      (node (ref "U1") (pin "18") (pinfunction "TXD1_18") (pintype "passive"))
      (node (ref "U3") (pin "33") (pinfunction "PC4/ADC14_33") (pintype "bidirectional"))
    )
    (net (code "54") (name "/GPHY_RGMII_TXD2") (class "Default")
      (node (ref "P6") (pin "13") (pinfunction "13_13") (pintype "passive"))
      (node (ref "U1") (pin "17") (pinfunction "TXD2_17") (pintype "passive"))
      (node (ref "U3") (pin "34") (pinfunction "PC5/ADC15_34") (pintype "bidirectional"))
    )
    (net (code "55") (name "/GPHY_RGMII_TXD3") (class "Default")
      (node (ref "P6") (pin "14") (pinfunction "14_14") (pintype "passive"))
      (node (ref "U1") (pin "16") (pinfunction "TXD3_16") (pintype "passive"))
      (node (ref "U3") (pin "35") (pinfunction "PB0/ADC8_35") (pintype "bidirectional"))
    )
    (net (code "56") (name "/GPHY_RGMII_TXEN") (class "Default")
      (node (ref "P6") (pin "10") (pinfunction "10_10") (pintype "passive"))
      (node (ref "U1") (pin "20") (pinfunction "TXCTL_20") (pintype "passive"))
      (node (ref "U3") (pin "26") (pinfunction "PA3/ADC3_26") (pintype "bidirectional"))
    )
    (net (code "57") (name "/I2C2_SCL") (class "Default")
      (node (ref "P10") (pin "4") (pinfunction "4_4") (pintype "passive"))
      (node (ref "R51") (pin "1") (pinfunction "1_1") (pintype "passive"))
      (node (ref "S5") (pin "1") (pinfunction "1_1") (pintype "passive"))
      (node (ref "U3") (pin "47") (pinfunction "PB10_47") (pintype "bidirectional"))
    )
    (net (code "58") (name "/I2C2_SDA") (class "Default")
      (node (ref "P10") (pin "6") (pinfunction "6_6") (pintype "passive"))
      (node (ref "R52") (pin "1") (pinfunction "1_1") (pintype "passive"))
      (node (ref "S6") (pin "1") (pinfunction "1_1") (pintype "passive"))
      (node (ref "U3") (pin "48") (pinfunction "PB11_48") (pintype "bidirectional"))
    )
    (net (code "59") (name "/INTB") (class "Default")
      (node (ref "R16") (pin "1") (pintype "passive"))
      (node (ref "R17") (pin "1") (pintype "passive"))
      (node (ref "U1") (pin "34") (pinfunction "INTB/PMEB/GPIO1_34") (pintype "passive"))
    )
    (net (code "60") (name "/LCD_BLK") (class "Default")
      (node (ref "P3") (pin "5") (pinfunction "5_5") (pintype "passive"))
      (node (ref "U3") (pin "2") (pinfunction "PE3_2") (pintype "bidirectional"))
    )
    (net (code "61") (name "/LCD_CS1") (class "Default")
      (node (ref "P3") (pin "3") (pinfunction "3_3") (pintype "passive"))
      (node (ref "U3") (pin "3") (pinfunction "PE4_3") (pintype "bidirectional"))
    )
    (net (code "62") (name "/LCD_CS2") (class "Default")
      (node (ref "P3") (pin "2") (pinfunction "2_2") (pintype "passive"))
      (node (ref "U3") (pin "4") (pinfunction "PE5_4") (pintype "bidirectional"))
    )
    (net (code "63") (name "/LCD_DC") (class "Default")
      (node (ref "P3") (pin "6") (pinfunction "6_6") (pintype "passive"))
      (node (ref "U3") (pin "1") (pinfunction "PE2_1") (pintype "bidirectional"))
    )
    (net (code "64") (name "/LCD_INT") (class "Default")
      (node (ref "P3") (pin "1") (pinfunction "1_1") (pintype "passive"))
      (node (ref "U3") (pin "5") (pinfunction "PE6_5") (pintype "bidirectional"))
      (node (ref "U5") (pin "1") (pinfunction "CS#_1") (pintype "input"))
    )
    (net (code "65") (name "/LCD_RST") (class "Default")
      (node (ref "P3") (pin "7") (pinfunction "7_7") (pintype "passive"))
      (node (ref "U3") (pin "77") (pinfunction "PA15_77") (pintype "bidirectional"))
    )
    (net (code "66") (name "/LCD_VCC") (class "Default")
      (node (ref "F2") (pin "1") (pinfunction "1_1") (pintype "passive"))
      (node (ref "P3") (pin "10") (pinfunction "10_10") (pintype "passive"))
    )
    (net (code "67") (name "/LED0{slash}PHYAD0") (class "Default")
      (node (ref "C25") (pin "1") (pinfunction "1_1") (pintype "passive"))
      (node (ref "R30") (pin "2") (pintype "passive"))
      (node (ref "R33") (pin "2") (pintype "passive"))
      (node (ref "U1") (pin "35") (pinfunction "LED0/PHYAD0_35") (pintype "passive"))
    )
    (net (code "68") (name "/LED1{slash}CFG_LDO0") (class "Default")
      (node (ref "C29") (pin "1") (pinfunction "1_1") (pintype "passive"))
      (node (ref "R22") (pin "1") (pintype "passive"))
      (node (ref "R40") (pin "2") (pintype "passive"))
      (node (ref "U1") (pin "36") (pinfunction "LED1/CFG_LDO0_36") (pintype "passive"))
    )
    (net (code "69") (name "/LED2{slash}CFG_LDO1") (class "Default")
      (node (ref "C18") (pin "1") (pinfunction "1_1") (pintype "passive"))
      (node (ref "R19") (pin "2") (pintype "passive"))
      (node (ref "R26") (pin "1") (pintype "passive"))
      (node (ref "U1") (pin "37") (pinfunction "LED2/CFG_LDO1_37") (pintype "passive"))
    )
    (net (code "70") (name "/LED_blue_n") (class "Default")
      (node (ref "D1") (pin "K") (pinfunction "K_K") (pintype "passive"))
      (node (ref "R23") (pin "1") (pintype "passive"))
    )
    (net (code "71") (name "/LED_blue_p") (class "Default")
      (node (ref "D1") (pin "A") (pinfunction "A_A") (pintype "passive"))
      (node (ref "R19") (pin "1") (pintype "passive"))
    )
    (net (code "72") (name "/LED_green_n") (class "Default")
      (node (ref "D3") (pin "K") (pinfunction "K_K") (pintype "passive"))
      (node (ref "P4") (pin "12") (pinfunction "24_12") (pintype "passive"))
      (node (ref "R47") (pin "1") (pintype "passive"))
    )
    (net (code "73") (name "/LED_green_p") (class "Default")
      (node (ref "D3") (pin "A") (pinfunction "A_A") (pintype "passive"))
      (node (ref "P4") (pin "11") (pinfunction "23_11") (pintype "passive"))
      (node (ref "R40") (pin "1") (pintype "passive"))
    )
    (net (code "74") (name "/LED_yellow_n") (class "Default")
      (node (ref "D2") (pin "K") (pinfunction "K_K") (pintype "passive"))
      (node (ref "P4") (pin "13") (pinfunction "24_13") (pintype "passive"))
      (node (ref "R30") (pin "1") (pintype "passive"))
    )
    (net (code "75") (name "/LED_yellow_p") (class "Default")
      (node (ref "D2") (pin "A") (pinfunction "A_A") (pintype "passive"))
      (node (ref "P4") (pin "14") (pinfunction "23_14") (pintype "passive"))
      (node (ref "R29") (pin "2") (pintype "passive"))
    )
    (net (code "76") (name "/MAC_125M") (class "Default")
      (node (ref "P6") (pin "15") (pinfunction "15_15") (pintype "passive"))
      (node (ref "U1") (pin "44") (pinfunction "CLKOUT_44") (pintype "passive"))
      (node (ref "U3") (pin "36") (pinfunction "PB1/ADC9_36") (pintype "bidirectional"))
    )
    (net (code "77") (name "/MDI0_n") (class "Default")
      (node (ref "P4") (pin "3") (pinfunction "MDI_0-_3") (pintype "passive"))
      (node (ref "U1") (pin "3") (pinfunction "MDI[0]-_3") (pintype "passive"))
    )
    (net (code "78") (name "/MDI0_p") (class "Default")
      (node (ref "P4") (pin "2") (pinfunction "MDI_0+_2") (pintype "passive"))
      (node (ref "U1") (pin "2") (pinfunction "MDI[0]+_2") (pintype "passive"))
    )
    (net (code "79") (name "/MDI1_n") (class "Default")
      (node (ref "P4") (pin "7") (pinfunction "MDI_1-_7") (pintype "passive"))
      (node (ref "U1") (pin "6") (pinfunction "MDI[1]-_6") (pintype "passive"))
    )
    (net (code "80") (name "/MDI1_p") (class "Default")
      (node (ref "P4") (pin "4") (pinfunction "MDI_1+_4") (pintype "passive"))
      (node (ref "U1") (pin "5") (pinfunction "MDI[1]+_5") (pintype "passive"))
    )
    (net (code "81") (name "/MDI2_n") (class "Default")
      (node (ref "P4") (pin "6") (pinfunction "MDI_2-_6") (pintype "passive"))
      (node (ref "U1") (pin "8") (pinfunction "MDI[2]-_8") (pintype "passive"))
    )
    (net (code "82") (name "/MDI2_p") (class "Default")
      (node (ref "P4") (pin "5") (pinfunction "MDI_2+_5") (pintype "passive"))
      (node (ref "U1") (pin "7") (pinfunction "MDI[2]+_7") (pintype "passive"))
    )
    (net (code "83") (name "/MDI3_n") (class "Default")
      (node (ref "P4") (pin "9") (pinfunction "MDI_3-_9") (pintype "passive"))
      (node (ref "U1") (pin "11") (pinfunction "MDI[3]-_11") (pintype "passive"))
    )
    (net (code "84") (name "/MDI3_p") (class "Default")
      (node (ref "P4") (pin "8") (pinfunction "MDI_3+_8") (pintype "passive"))
      (node (ref "U1") (pin "10") (pinfunction "MDI[3]+_10") (pintype "passive"))
    )
    (net (code "85") (name "/NRST") (class "Default")
      (node (ref "C17") (pin "2") (pinfunction "2_2") (pintype "passive"))
      (node (ref "P1") (pin "21") (pinfunction "21_21") (pintype "passive"))
      (node (ref "S1") (pin "2") (pinfunction "2_2") (pintype "passive"))
      (node (ref "U3") (pin "14") (pinfunction "NRST_14") (pintype "input"))
    )
    (net (code "86") (name "/PB6") (class "Default")
      (node (ref "P1") (pin "11") (pinfunction "11_11") (pintype "passive"))
      (node (ref "R3") (pin "2") (pinfunction "2_2") (pintype "passive"))
    )
    (net (code "87") (name "/PB7") (class "Default")
      (node (ref "P1") (pin "12") (pinfunction "12_12") (pintype "passive"))
      (node (ref "R1") (pin "2") (pinfunction "2_2") (pintype "passive"))
    )
    (net (code "88") (name "/PC14") (class "Default")
      (node (ref "P1") (pin "17") (pinfunction "17_17") (pintype "passive"))
      (node (ref "R56") (pin "2") (pinfunction "2_2") (pintype "passive"))
    )
    (net (code "89") (name "/PC15") (class "Default")
      (node (ref "P1") (pin "18") (pinfunction "18_18") (pintype "passive"))
      (node (ref "R59") (pin "2") (pinfunction "2_2") (pintype "passive"))
    )
    (net (code "90") (name "/PHY2_int") (class "Default")
      (node (ref "P2") (pin "21") (pinfunction "21_21") (pintype "passive"))
      (node (ref "R17") (pin "2") (pintype "passive"))
      (node (ref "U3") (pin "64") (pinfunction "PC7/RXN_64") (pintype "bidirectional"))
    )
    (net (code "91") (name "/PHY2_reset") (class "Default")
      (node (ref "P2") (pin "24") (pinfunction "24_24") (pintype "passive"))
      (node (ref "R12") (pin "2") (pintype "passive"))
      (node (ref "U3") (pin "63") (pinfunction "PC6/RXP_63") (pintype "bidirectional"))
    )
    (net (code "92") (name "/PHYRSTB") (class "Default")
      (node (ref "C7") (pin "2") (pinfunction "2_2") (pintype "passive"))
      (node (ref "R11") (pin "1") (pintype "passive"))
      (node (ref "R12") (pin "1") (pintype "passive"))
      (node (ref "U1") (pin "13") (pinfunction "PHYRSTB_13") (pintype "passive"))
    )
    (net (code "93") (name "/PVIN") (class "Default")
      (node (ref "F1") (pin "1") (pinfunction "1_1") (pintype "passive"))
      (node (ref "P1") (pin "25") (pinfunction "25_25") (pintype "passive"))
      (node (ref "P11") (pin "1") (pinfunction "+5V_1") (pintype "power_in"))
      (node (ref "P9") (pin "1") (pinfunction "+5V_1") (pintype "power_in"))
    )
    (net (code "94") (name "/REGOUT") (class "Default")
      (node (ref "L1") (pin "1") (pinfunction "1_1") (pintype "passive"))
      (node (ref "U1") (pin "32") (pinfunction "REGOUT_32") (pintype "power_in"))
    )
    (net (code "95") (name "/RGMII_MDC") (class "Default")
      (node (ref "P6") (pin "16") (pinfunction "16_16") (pintype "passive"))
      (node (ref "U1") (pin "14") (pinfunction "MDC_14") (pintype "passive"))
      (node (ref "U3") (pin "51") (pinfunction "PB12_51") (pintype "bidirectional"))
    )
    (net (code "96") (name "/RGMII_MDIO") (class "Default")
      (node (ref "P6") (pin "17") (pinfunction "17_17") (pintype "passive"))
      (node (ref "R5") (pin "2") (pintype "passive"))
      (node (ref "U1") (pin "15") (pinfunction "MDIO_15") (pintype "passive"))
      (node (ref "U3") (pin "52") (pinfunction "PB13_52") (pintype "bidirectional"))
    )
    (net (code "97") (name "/RSET") (class "Default")
      (node (ref "R2") (pin "1") (pintype "passive"))
      (node (ref "U1") (pin "48") (pinfunction "RSET_48") (pintype "passive"))
    )
    (net (code "98") (name "/SDIO_CLK") (class "Default")
      (node (ref "P1") (pin "2") (pinfunction "2_2") (pintype "passive"))
      (node (ref "P7") (pin "5") (pinfunction "CLK/SCLK_5") (pintype "passive"))
      (node (ref "U3") (pin "80") (pinfunction "PC12_80") (pintype "bidirectional"))
    )
    (net (code "99") (name "/SDIO_CMD") (class "Default")
      (node (ref "P1") (pin "5") (pinfunction "5_5") (pintype "passive"))
      (node (ref "P7") (pin "3") (pinfunction "CMD/DI_3") (pintype "passive"))
      (node (ref "R6") (pin "1") (pinfunction "1_1") (pintype "passive"))
      (node (ref "U3") (pin "83") (pinfunction "PD2_83") (pintype "bidirectional"))
    )
    (net (code "100") (name "/SDIO_D2") (class "Default")
      (node (ref "P1") (pin "1") (pinfunction "1_1") (pintype "passive"))
      (node (ref "P7") (pin "1") (pinfunction "DAT2/RSV_1") (pintype "passive"))
      (node (ref "R10") (pin "1") (pinfunction "1_1") (pintype "passive"))
      (node (ref "U3") (pin "78") (pinfunction "PC10_78") (pintype "bidirectional"))
    )
    (net (code "101") (name "/SPI3_MISO") (class "Default")
      (node (ref "P3") (pin "4") (pinfunction "4_4") (pintype "passive"))
      (node (ref "U3") (pin "90") (pinfunction "PB4_90") (pintype "bidirectional"))
      (node (ref "U5") (pin "2") (pinfunction "SDO_2") (pintype "output"))
    )
    (net (code "102") (name "/SPI3_MOSI") (class "Default")
      (node (ref "P3") (pin "8") (pinfunction "8_8") (pintype "passive"))
      (node (ref "U3") (pin "91") (pinfunction "PB5_91") (pintype "bidirectional"))
      (node (ref "U5") (pin "5") (pinfunction "SDI_5") (pintype "input"))
    )
    (net (code "103") (name "/SPI3_SCK") (class "Default")
      (node (ref "P3") (pin "9") (pinfunction "9_9") (pintype "passive"))
      (node (ref "U3") (pin "89") (pinfunction "PB3_89") (pintype "bidirectional"))
      (node (ref "U5") (pin "6") (pinfunction "SCK_6") (pintype "input"))
    )
    (net (code "104") (name "/SWDCK") (class "Default")
      (node (ref "P2") (pin "1") (pinfunction "1_1") (pintype "passive"))
      (node (ref "U3") (pin "76") (pinfunction "PA14/SWCLK_76") (pintype "bidirectional"))
    )
    (net (code "105") (name "/SWDIO") (class "Default")
      (node (ref "P2") (pin "3") (pinfunction "3_3") (pintype "passive"))
      (node (ref "U3") (pin "72") (pinfunction "PA13/SWDIO_72") (pintype "bidirectional"))
    )
    (net (code "106") (name "/U1_RX{slash}DVP_D1") (class "Default")
      (node (ref "P10") (pin "9") (pinfunction "9_9") (pintype "passive"))
      (node (ref "R44") (pin "2") (pinfunction "2_2") (pintype "passive"))
      (node (ref "U3") (pin "69") (pinfunction "PA10_69") (pintype "bidirectional"))
    )
    (net (code "107") (name "/U1_TX{slash}DVP_D0") (class "Default")
      (node (ref "P10") (pin "8") (pinfunction "8_8") (pintype "passive"))
      (node (ref "R35") (pin "2") (pinfunction "2_2") (pintype "passive"))
      (node (ref "U3") (pin "68") (pinfunction "PA9_68") (pintype "bidirectional"))
    )
    (net (code "108") (name "/UART1_TX_2") (class "Default")
      (node (ref "R46") (pin "2") (pinfunction "2_2") (pintype "passive"))
      (node (ref "U3") (pin "54") (pinfunction "PB15_54") (pintype "bidirectional"))
    )
    (net (code "109") (name "/USB1D_n") (class "Default")
      (node (ref "P2") (pin "19") (pinfunction "19_19") (pintype "passive"))
      (node (ref "P9") (pin "2") (pinfunction "UD-_2") (pintype "bidirectional"))
      (node (ref "U3") (pin "70") (pinfunction "PA11/USB1DM_70") (pintype "bidirectional"))
    )
    (net (code "110") (name "/USB1D_p") (class "Default")
      (node (ref "P2") (pin "20") (pinfunction "20_20") (pintype "passive"))
      (node (ref "P9") (pin "3") (pinfunction "UD+_3") (pintype "bidirectional"))
      (node (ref "U3") (pin "71") (pinfunction "PA12/USB1DP_71") (pintype "bidirectional"))
    )
    (net (code "111") (name "/USB2D_n") (class "Default")
      (node (ref "P11") (pin "2") (pinfunction "UD-_2") (pintype "bidirectional"))
      (node (ref "R3") (pin "1") (pinfunction "1_1") (pintype "passive"))
      (node (ref "R53") (pin "1") (pinfunction "1_1") (pintype "passive"))
      (node (ref "U3") (pin "92") (pinfunction "PB6/USB2DM_92") (pintype "bidirectional"))
    )
    (net (code "112") (name "/USB2D_p") (class "Default")
      (node (ref "P11") (pin "3") (pinfunction "UD+_3") (pintype "bidirectional"))
      (node (ref "R1") (pin "1") (pinfunction "1_1") (pintype "passive"))
      (node (ref "U3") (pin "93") (pinfunction "PB7/USB2DP_93") (pintype "bidirectional"))
    )
    (net (code "113") (name "/VBAT") (class "Default")
      (node (ref "C30") (pin "2") (pinfunction "2_2") (pintype "passive"))
      (node (ref "P1") (pin "29") (pinfunction "29_29") (pintype "passive"))
      (node (ref "U3") (pin "6") (pinfunction "VBAT_6") (pintype "power_in"))
    )
    (net (code "114") (name "/VDD") (class "Default")
      (node (ref "C26") (pin "2") (pinfunction "2_2") (pintype "passive"))
      (node (ref "C31") (pin "1") (pinfunction "1_1") (pintype "passive"))
      (node (ref "C38") (pin "2") (pinfunction "2_2") (pintype "passive"))
      (node (ref "P1") (pin "31") (pinfunction "31_31") (pintype "passive"))
      (node (ref "P2") (pin "7") (pinfunction "7_7") (pintype "passive"))
      (node (ref "P2") (pin "8") (pinfunction "8_8") (pintype "passive"))
      (node (ref "U3") (pin "11") (pinfunction "VDD_5_11") (pintype "power_in"))
      (node (ref "U3") (pin "28") (pinfunction "VDD_4_28") (pintype "power_in"))
      (node (ref "U3") (pin "75") (pinfunction "VDD_2_75") (pintype "power_in"))
    )
    (net (code "115") (name "/VDDA") (class "Default")
      (node (ref "C33") (pin "1") (pinfunction "1_1") (pintype "passive"))
      (node (ref "R55") (pin "1") (pinfunction "1_1") (pintype "passive"))
      (node (ref "R57") (pin "2") (pinfunction "2_2") (pintype "passive"))
      (node (ref "U3") (pin "22") (pinfunction "VDDA_22") (pintype "power_in"))
    )
    (net (code "116") (name "/VIO") (class "Default")
      (node (ref "C19") (pin "1") (pinfunction "1_1") (pintype "passive"))
      (node (ref "C37") (pin "2") (pinfunction "2_2") (pintype "passive"))
      (node (ref "P1") (pin "33") (pinfunction "33_33") (pintype "passive"))
      (node (ref "P1") (pin "35") (pinfunction "35_35") (pintype "passive"))
      (node (ref "P1") (pin "36") (pinfunction "36_36") (pintype "passive"))
      (node (ref "R57") (pin "1") (pinfunction "1_1") (pintype "passive"))
      (node (ref "U3") (pin "100") (pinfunction "VIO_3_100") (pintype "power_in"))
      (node (ref "U3") (pin "50") (pinfunction "VIO_1_50") (pintype "power_in"))
    )
    (net (code "117") (name "/VREF+") (class "Default")
      (node (ref "P1") (pin "24") (pinfunction "24_24") (pintype "passive"))
      (node (ref "R55") (pin "2") (pinfunction "2_2") (pintype "passive"))
      (node (ref "U3") (pin "21") (pinfunction "VREF+_21") (pintype "power_in"))
    )
    (net (code "118") (name "/VREF-") (class "Default")
      (node (ref "P1") (pin "23") (pinfunction "23_23") (pintype "passive"))
      (node (ref "R54") (pin "2") (pinfunction "2_2") (pintype "passive"))
      (node (ref "U3") (pin "20") (pinfunction "VREF-_20") (pintype "power_in"))
    )
    (net (code "119") (name "/X32KI") (class "Default")
      (node (ref "C11") (pin "2") (pinfunction "2_2") (pintype "passive"))
      (node (ref "R56") (pin "1") (pinfunction "1_1") (pintype "passive"))
      (node (ref "U3") (pin "8") (pinfunction "PC14/OSC32IN_8") (pintype "bidirectional"))
      (node (ref "Y1") (pin "1") (pinfunction "OSC1_1") (pintype "passive"))
    )
    (net (code "120") (name "/X32KO") (class "Default")
      (node (ref "C12") (pin "2") (pinfunction "2_2") (pintype "passive"))
      (node (ref "R59") (pin "1") (pinfunction "1_1") (pintype "passive"))
      (node (ref "U3") (pin "9") (pinfunction "PC15/OSC32OUT_9") (pintype "bidirectional"))
      (node (ref "Y1") (pin "2") (pinfunction "OSC2_2") (pintype "passive"))
    )
    (net (code "121") (name "/XI") (class "Default")
      (node (ref "C15") (pin "2") (pinfunction "2_2") (pintype "passive"))
      (node (ref "U3") (pin "12") (pinfunction "OSC_IN_12") (pintype "input"))
      (node (ref "Y2") (pin "1") (pinfunction "OSC1_1") (pintype "passive"))
    )
    (net (code "122") (name "/XO") (class "Default")
      (node (ref "C16") (pin "2") (pinfunction "2_2") (pintype "passive"))
      (node (ref "U3") (pin "13") (pinfunction "OSC_OUT_13") (pintype "output"))
      (node (ref "Y2") (pin "3") (pinfunction "OSC2_3") (pintype "passive"))
    )
    (net (code "123") (name "/XTAL1") (class "Default")
      (node (ref "C13") (pin "2") (pinfunction "2_2") (pintype "passive"))
      (node (ref "R14") (pin "1") (pintype "passive"))
      (node (ref "U1") (pin "46") (pinfunction "XTAL_OUT/EXT_CLK_46") (pintype "passive"))
      (node (ref "X1") (pin "3") (pinfunction "3_3") (pintype "passive"))
    )
    (net (code "124") (name "/XTAL2") (class "Default")
      (node (ref "C14") (pin "2") (pinfunction "2_2") (pintype "passive"))
      (node (ref "U1") (pin "45") (pinfunction "XTAL_IN_45") (pintype "passive"))
      (node (ref "X1") (pin "1") (pinfunction "1_1") (pintype "passive"))
    )
    (net (code "125") (name "3V3") (class "Default")
      (node (ref "C20") (pin "2") (pinfunction "2_2") (pintype "passive"))
      (node (ref "C21") (pin "2") (pinfunction "2_2") (pintype "passive"))
      (node (ref "C22") (pin "2") (pinfunction "2_2") (pintype "passive"))
      (node (ref "C23") (pin "2") (pinfunction "2_2") (pintype "passive"))
      (node (ref "C24") (pin "2") (pinfunction "2_2") (pintype "passive"))
      (node (ref "C27") (pin "2") (pinfunction "2_2") (pintype "passive"))
      (node (ref "C28") (pin "2") (pinfunction "2_2") (pintype "passive"))
      (node (ref "C35") (pin "2") (pinfunction "2_2") (pintype "passive"))
      (node (ref "C36") (pin "2") (pinfunction "2_2") (pintype "passive"))
      (node (ref "C39") (pin "1") (pinfunction "1_1") (pintype "passive"))
      (node (ref "C41") (pin "1") (pinfunction "1_1") (pintype "passive"))
      (node (ref "D5") (pin "A") (pinfunction "A_A") (pintype "passive"))
      (node (ref "F2") (pin "2") (pinfunction "2_2") (pintype "passive"))
      (node (ref "F3") (pin "2") (pinfunction "2_2") (pintype "passive"))
      (node (ref "P1") (pin "30") (pinfunction "30_30") (pintype "passive"))
      (node (ref "P1") (pin "32") (pinfunction "32_32") (pintype "passive"))
      (node (ref "P1") (pin "34") (pinfunction "34_34") (pintype "passive"))
      (node (ref "P7") (pin "4") (pinfunction "VDD_4") (pintype "passive"))
      (node (ref "R10") (pin "2") (pinfunction "2_2") (pintype "passive"))
      (node (ref "R11") (pin "2") (pintype "passive"))
      (node (ref "R13") (pin "2") (pintype "passive"))
      (node (ref "R16") (pin "2") (pintype "passive"))
      (node (ref "R18") (pin "2") (pinfunction "2_2") (pintype "passive"))
      (node (ref "R20") (pin "2") (pinfunction "2_2") (pintype "passive"))
      (node (ref "R29") (pin "1") (pintype "passive"))
      (node (ref "R33") (pin "1") (pintype "passive"))
      (node (ref "R5") (pin "1") (pintype "passive"))
      (node (ref "R51") (pin "2") (pinfunction "2_2") (pintype "passive"))
      (node (ref "R52") (pin "2") (pinfunction "2_2") (pintype "passive"))
      (node (ref "R6") (pin "2") (pinfunction "2_2") (pintype "passive"))
      (node (ref "R8") (pin "2") (pinfunction "2_2") (pintype "passive"))
      (node (ref "U1") (pin "1") (pinfunction "AVDD33_1_1") (pintype "power_in"))
      (node (ref "U1") (pin "12") (pinfunction "AVDD33_12_12") (pintype "power_in"))
      (node (ref "U1") (pin "30") (pinfunction "DVDD33_30_30") (pintype "power_in"))
      (node (ref "U1") (pin "31") (pinfunction "VDDREG_31") (pintype "power_in"))
      (node (ref "U4") (pin "2") (pinfunction "Vout_2") (pintype "passive"))
      (node (ref "U5") (pin "3") (pinfunction "WP#_3") (pintype "input"))
      (node (ref "U5") (pin "7") (pinfunction "HD#_7") (pintype "power_in"))
      (node (ref "U5") (pin "8") (pinfunction "VCC_8") (pintype "power_in"))
    )
    (net (code "126") (name "5V") (class "Default")
      (node (ref "C40") (pin "1") (pinfunction "1_1") (pintype "passive"))
      (node (ref "P2") (pin "10") (pinfunction "10_10") (pintype "passive"))
      (node (ref "P2") (pin "9") (pinfunction "9_9") (pintype "passive"))
      (node (ref "S2") (pin "2") (pinfunction "NC_2") (pintype "passive"))
      (node (ref "U4") (pin "3") (pinfunction "Vin_3") (pintype "passive"))
    )
    (net (code "127") (name "AVDD10") (class "Default")
      (node (ref "C1") (pin "2") (pinfunction "2_2") (pintype "passive"))
      (node (ref "C2") (pin "2") (pinfunction "2_2") (pintype "passive"))
      (node (ref "C3") (pin "2") (pinfunction "2_2") (pintype "passive"))
      (node (ref "C4") (pin "2") (pinfunction "2_2") (pintype "passive"))
      (node (ref "C5") (pin "2") (pinfunction "2_2") (pintype "passive"))
      (node (ref "C6") (pin "2") (pinfunction "2_2") (pintype "passive"))
      (node (ref "L1") (pin "2") (pinfunction "2_2") (pintype "passive"))
      (node (ref "U1") (pin "22") (pinfunction "DVDD10_22") (pintype "power_in"))
      (node (ref "U1") (pin "4") (pinfunction "AVDD10_4_4") (pintype "power_in"))
      (node (ref "U1") (pin "47") (pinfunction "AVDD10_47_47") (pintype "power_in"))
      (node (ref "U1") (pin "9") (pinfunction "AVDD10_9_9") (pintype "power_in"))
    )
    (net (code "128") (name "GND") (class "Default")
      (node (ref "C1") (pin "1") (pinfunction "1_1") (pintype "passive"))
      (node (ref "C10") (pin "2") (pinfunction "2_2") (pintype "passive"))
      (node (ref "C11") (pin "1") (pinfunction "1_1") (pintype "passive"))
      (node (ref "C12") (pin "1") (pinfunction "1_1") (pintype "passive"))
      (node (ref "C13") (pin "1") (pinfunction "1_1") (pintype "passive"))
      (node (ref "C14") (pin "1") (pinfunction "1_1") (pintype "passive"))
      (node (ref "C15") (pin "1") (pinfunction "1_1") (pintype "passive"))
      (node (ref "C16") (pin "1") (pinfunction "1_1") (pintype "passive"))
      (node (ref "C17") (pin "1") (pinfunction "1_1") (pintype "passive"))
      (node (ref "C18") (pin "2") (pinfunction "2_2") (pintype "passive"))
      (node (ref "C19") (pin "2") (pinfunction "2_2") (pintype "passive"))
      (node (ref "C2") (pin "1") (pinfunction "1_1") (pintype "passive"))
      (node (ref "C20") (pin "1") (pinfunction "1_1") (pintype "passive"))
      (node (ref "C21") (pin "1") (pinfunction "1_1") (pintype "passive"))
      (node (ref "C22") (pin "1") (pinfunction "1_1") (pintype "passive"))
      (node (ref "C23") (pin "1") (pinfunction "1_1") (pintype "passive"))
      (node (ref "C24") (pin "1") (pinfunction "1_1") (pintype "passive"))
      (node (ref "C25") (pin "2") (pinfunction "2_2") (pintype "passive"))
      (node (ref "C26") (pin "1") (pinfunction "1_1") (pintype "passive"))
      (node (ref "C27") (pin "1") (pinfunction "1_1") (pintype "passive"))
      (node (ref "C28") (pin "1") (pinfunction "1_1") (pintype "passive"))
      (node (ref "C29") (pin "2") (pinfunction "2_2") (pintype "passive"))
      (node (ref "C3") (pin "1") (pinfunction "1_1") (pintype "passive"))
      (node (ref "C30") (pin "1") (pinfunction "1_1") (pintype "passive"))
      (node (ref "C31") (pin "2") (pinfunction "2_2") (pintype "passive"))
      (node (ref "C32") (pin "1") (pinfunction "1_1") (pintype "passive"))
      (node (ref "C33") (pin "2") (pinfunction "2_2") (pintype "passive"))
      (node (ref "C34") (pin "1") (pinfunction "1_1") (pintype "passive"))
      (node (ref "C35") (pin "1") (pinfunction "1_1") (pintype "passive"))
      (node (ref "C36") (pin "1") (pinfunction "1_1") (pintype "passive"))
      (node (ref "C37") (pin "1") (pinfunction "1_1") (pintype "passive"))
      (node (ref "C38") (pin "1") (pinfunction "1_1") (pintype "passive"))
      (node (ref "C39") (pin "2") (pinfunction "2_2") (pintype "passive"))
      (node (ref "C4") (pin "1") (pinfunction "1_1") (pintype "passive"))
      (node (ref "C40") (pin "2") (pinfunction "2_2") (pintype "passive"))
      (node (ref "C41") (pin "2") (pinfunction "2_2") (pintype "passive"))
      (node (ref "C5") (pin "1") (pinfunction "1_1") (pintype "passive"))
      (node (ref "C6") (pin "1") (pinfunction "1_1") (pintype "passive"))
      (node (ref "C7") (pin "1") (pinfunction "1_1") (pintype "passive"))
      (node (ref "C8") (pin "1") (pinfunction "1_1") (pintype "passive"))
      (node (ref "C9") (pin "1") (pinfunction "1_1") (pintype "passive"))
      (node (ref "P1") (pin "15") (pinfunction "15_15") (pintype "passive"))
      (node (ref "P1") (pin "16") (pinfunction "16_16") (pintype "passive"))
      (node (ref "P1") (pin "19") (pinfunction "19_19") (pintype "passive"))
      (node (ref "P1") (pin "20") (pinfunction "20_20") (pintype "passive"))
      (node (ref "P1") (pin "22") (pinfunction "22_22") (pintype "passive"))
      (node (ref "P1") (pin "26") (pinfunction "26_26") (pintype "passive"))
      (node (ref "P1") (pin "27") (pinfunction "27_27") (pintype "passive"))
      (node (ref "P1") (pin "28") (pinfunction "28_28") (pintype "passive"))
      (node (ref "P1") (pin "39") (pinfunction "39_39") (pintype "passive"))
      (node (ref "P1") (pin "40") (pinfunction "40_40") (pintype "passive"))
      (node (ref "P10") (pin "17") (pinfunction "17_17") (pintype "passive"))
      (node (ref "P10") (pin "2") (pinfunction "2_2") (pintype "passive"))
      (node (ref "P11") (pin "4") (pinfunction "GND_4") (pintype "power_in"))
      (node (ref "P11") (pin "5") (pinfunction "GND_5") (pintype "power_in"))
      (node (ref "P11") (pin "6") (pinfunction "GND_6") (pintype "power_in"))
      (node (ref "P2") (pin "11") (pinfunction "11_11") (pintype "passive"))
      (node (ref "P2") (pin "12") (pinfunction "12_12") (pintype "passive"))
      (node (ref "P2") (pin "13") (pinfunction "13_13") (pintype "passive"))
      (node (ref "P2") (pin "14") (pinfunction "14_14") (pintype "passive"))
      (node (ref "P2") (pin "15") (pinfunction "15_15") (pintype "passive"))
      (node (ref "P2") (pin "16") (pinfunction "16_16") (pintype "passive"))
      (node (ref "P2") (pin "17") (pinfunction "17_17") (pintype "passive"))
      (node (ref "P2") (pin "18") (pinfunction "18_18") (pintype "passive"))
      (node (ref "P2") (pin "22") (pinfunction "22_22") (pintype "passive"))
      (node (ref "P2") (pin "5") (pinfunction "5_5") (pintype "passive"))
      (node (ref "P2") (pin "6") (pinfunction "6_6") (pintype "passive"))
      (node (ref "P3") (pin "11") (pinfunction "11_11") (pintype "passive"))
      (node (ref "P6") (pin "1") (pinfunction "1_1") (pintype "passive"))
      (node (ref "P6") (pin "19") (pinfunction "19_19") (pintype "passive"))
      (node (ref "P6") (pin "2") (pinfunction "2_2") (pintype "passive"))
      (node (ref "P6") (pin "20") (pinfunction "20_20") (pintype "passive"))
      (node (ref "P7") (pin "10") (pinfunction "GND_10") (pintype "passive"))
      (node (ref "P7") (pin "6") (pinfunction "VSS_6") (pintype "passive"))
      (node (ref "P9") (pin "4") (pinfunction "GND_4") (pintype "power_in"))
      (node (ref "P9") (pin "5") (pinfunction "GND_5") (pintype "power_in"))
      (node (ref "P9") (pin "6") (pinfunction "GND_6") (pintype "power_in"))
      (node (ref "R15") (pin "2") (pintype "passive"))
      (node (ref "R2") (pin "2") (pintype "passive"))
      (node (ref "R22") (pin "2") (pintype "passive"))
      (node (ref "R23") (pin "2") (pintype "passive"))
      (node (ref "R26") (pin "2") (pintype "passive"))
      (node (ref "R38") (pin "2") (pintype "passive"))
      (node (ref "R4") (pin "2") (pintype "passive"))
      (node (ref "R43") (pin "2") (pintype "passive"))
      (node (ref "R47") (pin "2") (pintype "passive"))
      (node (ref "R54") (pin "1") (pinfunction "1_1") (pintype "passive"))
      (node (ref "R58") (pin "1") (pinfunction "1_1") (pintype "passive"))
      (node (ref "R7") (pin "2") (pintype "passive"))
      (node (ref "R9") (pin "2") (pintype "passive"))
      (node (ref "S1") (pin "1") (pinfunction "1_1") (pintype "passive"))
      (node (ref "S3") (pin "2") (pinfunction "2_2") (pintype "passive"))
      (node (ref "S4") (pin "2") (pinfunction "2_2") (pintype "passive"))
      (node (ref "S5") (pin "2") (pinfunction "2_2") (pintype "passive"))
      (node (ref "S6") (pin "2") (pinfunction "2_2") (pintype "passive"))
      (node (ref "S7") (pin "3") (pinfunction "3_3") (pintype "passive"))
      (node (ref "U1") (pin "49") (pinfunction "EGND_49") (pintype "passive"))
      (node (ref "U3") (pin "10") (pinfunction "VSS_5_10") (pintype "power_in"))
      (node (ref "U3") (pin "19") (pinfunction "VSSA_19") (pintype "power_in"))
      (node (ref "U3") (pin "27") (pinfunction "VSS_4_27") (pintype "power_in"))
      (node (ref "U3") (pin "49") (pinfunction "VSS_1_49") (pintype "power_in"))
      (node (ref "U3") (pin "74") (pinfunction "VSS_2_74") (pintype "power_in"))
      (node (ref "U3") (pin "99") (pinfunction "VSS_3_99") (pintype "power_in"))
      (node (ref "U4") (pin "1") (pinfunction "GND_1") (pintype "passive"))
      (node (ref "U5") (pin "4") (pinfunction "GND_4") (pintype "power_in"))
    )
    (net (code "129") (name "Net-(D5-PadK)") (class "Default")
      (node (ref "D5") (pin "K") (pinfunction "K_K") (pintype "passive"))
      (node (ref "R58") (pin "2") (pinfunction "2_2") (pintype "passive"))
    )
    (net (code "130") (name "Net-(F3-Pad1)") (class "Default")
      (node (ref "F3") (pin "1") (pinfunction "1_1") (pintype "passive"))
      (node (ref "P10") (pin "1") (pinfunction "1_1") (pintype "passive"))
    )
    (net (code "131") (name "Net-(P2-Pad2)") (class "Default")
      (node (ref "P2") (pin "2") (pinfunction "2_2") (pintype "passive"))
      (node (ref "R35") (pin "1") (pinfunction "1_1") (pintype "passive"))
      (node (ref "R46") (pin "1") (pinfunction "1_1") (pintype "passive"))
    )
    (net (code "132") (name "Net-(P2-Pad4)") (class "Default")
      (node (ref "P2") (pin "4") (pinfunction "4_4") (pintype "passive"))
      (node (ref "R44") (pin "1") (pinfunction "1_1") (pintype "passive"))
      (node (ref "R48") (pin "1") (pinfunction "1_1") (pintype "passive"))
    )
    (net (code "133") (name "Net-(P4-GND)") (class "Default")
      (node (ref "P4") (pin "10") (pinfunction "GND_10") (pintype "passive"))
      (node (ref "R15") (pin "1") (pintype "passive"))
    )
    (net (code "134") (name "Net-(P4-VCC)") (class "Default")
      (node (ref "C10") (pin "1") (pinfunction "1_1") (pintype "passive"))
      (node (ref "P4") (pin "1") (pinfunction "VCC_1") (pintype "passive"))
    )
    (net (code "135") (name "Net-(S2-COMMON)") (class "Default")
      (node (ref "F1") (pin "2") (pinfunction "2_2") (pintype "passive"))
      (node (ref "S2") (pin "1") (pinfunction "COMMON_1") (pintype "passive"))
    )
    (net (code "136") (name "unconnected-(P7-C{slash}D-Pad9)") (class "Default")
      (node (ref "P7") (pin "9") (pinfunction "C/D_9") (pintype "passive"))
    )
    (net (code "137") (name "unconnected-(S2-NO-Pad3)") (class "Default")
      (node (ref "S2") (pin "3") (pinfunction "NO_3") (pintype "passive"))
    )
    (net (code "138") (name "unconnected-(U1-HSIN-Pad39)") (class "Default")
      (node (ref "U1") (pin "39") (pinfunction "HSIN_39") (pintype "passive"))
    )
    (net (code "139") (name "unconnected-(U1-HSIP-Pad38)") (class "Default")
      (node (ref "U1") (pin "38") (pinfunction "HSIP_38") (pintype "passive"))
    )
    (net (code "140") (name "unconnected-(U1-HSON-Pad41)") (class "Default")
      (node (ref "U1") (pin "41") (pinfunction "HSON_41") (pintype "passive"))
    )
    (net (code "141") (name "unconnected-(U1-HSON_CLK-Pad43)") (class "Default")
      (node (ref "U1") (pin "43") (pinfunction "HSON_CLK_43") (pintype "passive"))
    )
    (net (code "142") (name "unconnected-(U1-HSOP-Pad40)") (class "Default")
      (node (ref "U1") (pin "40") (pinfunction "HSOP_40") (pintype "passive"))
    )
    (net (code "143") (name "unconnected-(U1-HSOP_CLK-Pad42)") (class "Default")
      (node (ref "U1") (pin "42") (pinfunction "HSOP_CLK_42") (pintype "passive"))
    )
    (net (code "144") (name "unconnected-(U1-PTP_CLKIN{slash}GPIO0-Pad33)") (class "Default")
      (node (ref "U1") (pin "33") (pinfunction "PTP_CLKIN/GPIO0_33") (pintype "passive"))
    )
    (net (code "145") (name "unconnected-(U3-NC-Pad73)") (class "Default")
      (node (ref "U3") (pin "73") (pinfunction "NC_73") (pintype "tri_state"))
    )
  )
)
